# IoTSchem.net
KiCad netlist of a schematic drawn in EAGLE
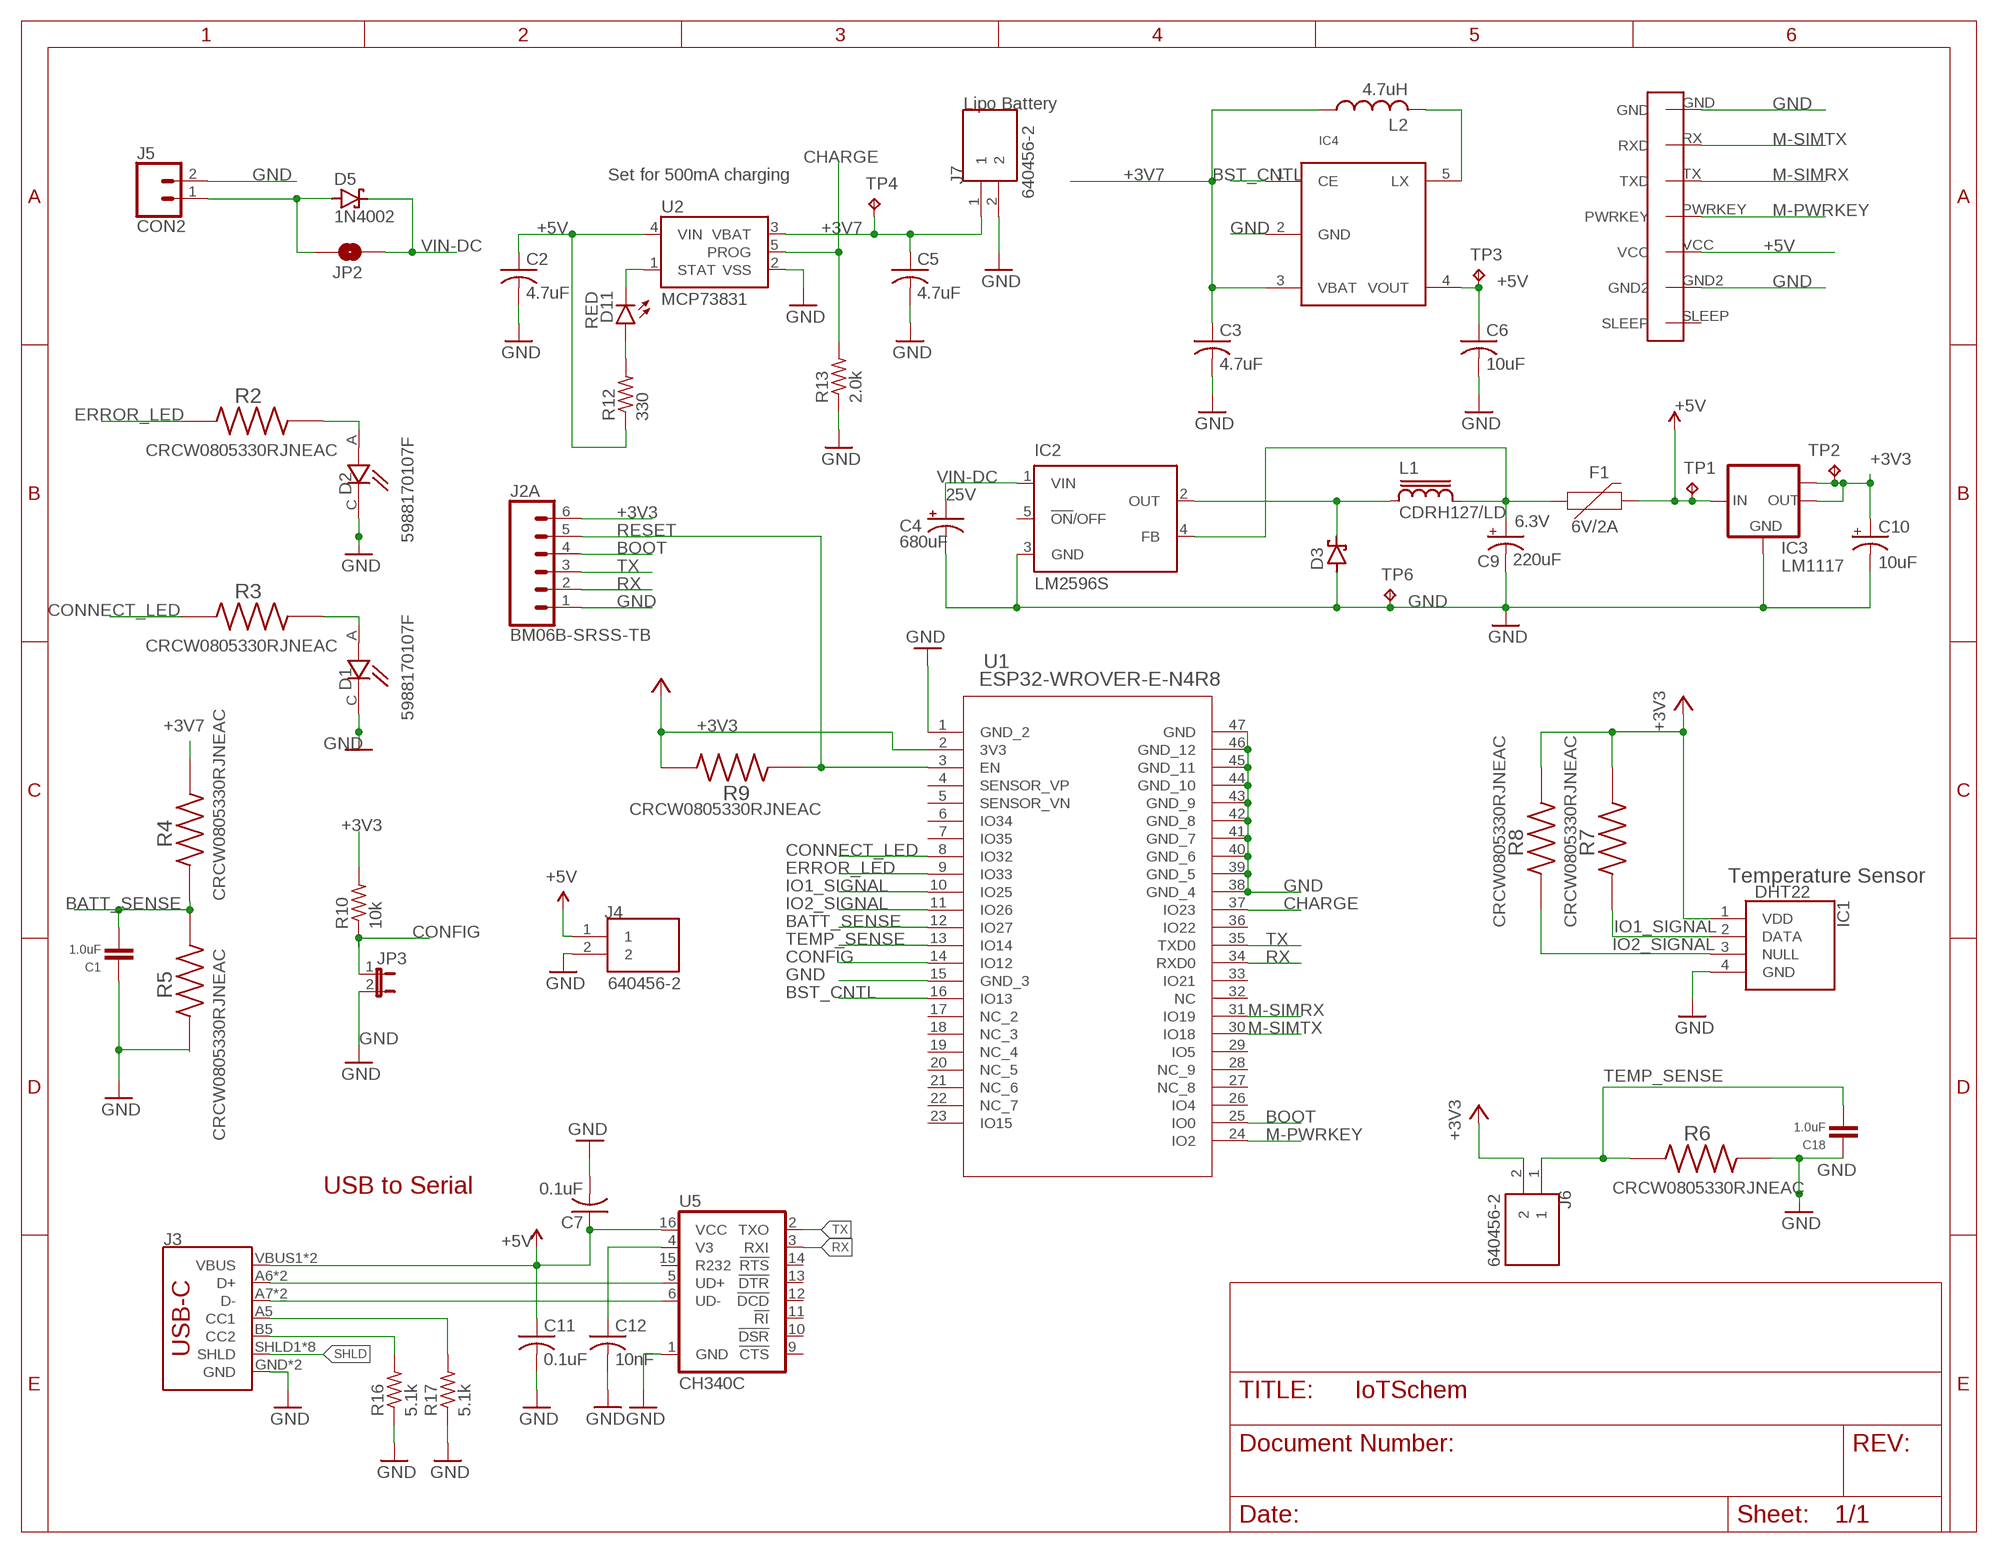
[diagram p0: schematic, sheet 1]

(export (version "E")
  (design (tool "Eeschema 10.0.6"))
  (components
    (comp (ref "C1")
      (value "1.0uF")
      (footprint "eagle-import:0805")
      (libsource (lib "eagle-import") (part "1.0UF-0805-25V-(+80/-20%)"))
    )
    (comp (ref "C2")
      (value "4.7uF")
      (footprint "eagle-import:C0603")
      (libsource (lib "eagle-import") (part "C-USC0603"))
    )
    (comp (ref "C3")
      (value "4.7uF")
      (footprint "eagle-import:C0805")
      (libsource (lib "eagle-import") (part "C-USC0805"))
    )
    (comp (ref "C4")
      (value "680uF")
      (footprint "eagle-import:E5-10,5")
      (fields (field (name "VOLTAGE") "25V"))
      (libsource (lib "eagle-import") (part "CPOL-USE5-10.5"))
    )
    (comp (ref "C5")
      (value "4.7uF")
      (footprint "eagle-import:C0603")
      (libsource (lib "eagle-import") (part "C-USC0603"))
    )
    (comp (ref "C6")
      (value "10uF")
      (footprint "eagle-import:C0805")
      (libsource (lib "eagle-import") (part "C-USC0805"))
    )
    (comp (ref "C7")
      (value "0.1uF")
      (footprint "eagle-import:C0805")
      (libsource (lib "eagle-import") (part "C-USC0805"))
    )
    (comp (ref "C9")
      (value "220uF")
      (footprint "eagle-import:UD-6,3X5,8_NICHICON")
      (fields (field (name "VOLTAGE") "6.3V"))
      (libsource (lib "eagle-import") (part "CPOL-USUD-6,3X5,8"))
    )
    (comp (ref "C10")
      (value "10uF")
      (footprint "eagle-import:EIA3216")
      (libsource (lib "eagle-import") (part "10UF-POLAR-EIA3216-16V-10%(TANT)"))
    )
    (comp (ref "C11")
      (value "0.1uF")
      (footprint "eagle-import:C0805")
      (libsource (lib "eagle-import") (part "C-USC0805"))
    )
    (comp (ref "C12")
      (value "10nF")
      (footprint "eagle-import:C0805")
      (libsource (lib "eagle-import") (part "C-USC0805"))
    )
    (comp (ref "C18")
      (value "1.0uF")
      (footprint "eagle-import:0805")
      (libsource (lib "eagle-import") (part "1.0UF-0805-25V-(+80/-20%)"))
    )
    (comp (ref "D1")
      (value "5988170107F")
      (footprint "eagle-import:LEDC2012X70N")
      (fields (field (name "DIGI-KEY_PART_NUMBER") "350-2044-1-ND") (field (name "MF") "Dialight"))
      (libsource (lib "eagle-import") (part "5988170107F"))
    )
    (comp (ref "D2")
      (value "5988170107F")
      (footprint "eagle-import:LEDC2012X70N")
      (fields (field (name "DIGI-KEY_PART_NUMBER") "350-2044-1-ND") (field (name "MF") "Dialight"))
      (libsource (lib "eagle-import") (part "5988170107F"))
    )
    (comp (ref "D3")
      (value "SCHOTTKY-DIODESMD")
      (footprint "eagle-import:SMB")
      (libsource (lib "eagle-import") (part "SCHOTTKY-DIODESMD"))
    )
    (comp (ref "D5")
      (value "1N4002")
      (footprint "eagle-import:SMB")
      (libsource (lib "eagle-import") (part "SCHOTTKY-DIODESMD"))
    )
    (comp (ref "D11")
      (value "RED")
      (footprint "eagle-import:LED-0603@1")
      (libsource (lib "eagle-import") (part "LED-RED0603"))
    )
    (comp (ref "F1")
      (value "6V/2A")
      (footprint "eagle-import:1210")
      (libsource (lib "eagle-import") (part "PPTC_6V2A"))
    )
    (comp (ref "IC1")
      (value "DHT22")
      (footprint "eagle-import:DHT22")
      (libsource (lib "eagle-import") (part "DHT22"))
    )
    (comp (ref "IC2")
      (value "LM2596S")
      (footprint "eagle-import:TO263-5")
      (fields (field (name "MF") "NATIONAL SEMICONDUCTOR") (field (name "MPN") "LM2596S-ADJ/NOPB"))
      (libsource (lib "eagle-import") (part "LM2596S"))
    )
    (comp (ref "IC3")
      (value "LM1117MPX-3.3")
      (footprint "eagle-import:SOT223")
      (libsource (lib "eagle-import") (part "LM1117MPX-3.3"))
    )
    (comp (ref "IC4")
      (value "XC9140")
      (footprint "eagle-import:SOT-25")
      (libsource (lib "eagle-import") (part "XC9140"))
    )
    (comp (ref "J1")
      (value "SIM7000A")
      (footprint "eagle-import:SIM7000A")
      (libsource (lib "eagle-import") (part "SIM7000A"))
    )
    (comp (ref "J2")
      (value "BM06B-SRSS-TB")
      (footprint "eagle-import:JST-6-SMD-HORI-1.0MM")
      (libsource (lib "eagle-import") (part "JST_6_PIN_HORIZONTAL"))
    )
    (comp (ref "J3")
      (value "USB_C16PIN")
      (footprint "eagle-import:USB-C-16P")
      (libsource (lib "eagle-import") (part "USB_C16PIN"))
    )
    (comp (ref "J4")
      (value "640456-2")
      (footprint "eagle-import:TE_640456-2")
      (fields (field (name "DIGI-KEY_PART_NUMBER") "A1921-ND") (field (name "MF") "TE Connectivity"))
      (libsource (lib "eagle-import") (part "640456-2"))
    )
    (comp (ref "J5")
      (value "CON2")
      (footprint "eagle-import:1X02")
      (libsource (lib "eagle-import") (part "CONN_02"))
    )
    (comp (ref "J6")
      (value "640456-2")
      (footprint "eagle-import:TE_640456-2")
      (fields (field (name "DIGI-KEY_PART_NUMBER") "A1921-ND") (field (name "MF") "TE Connectivity"))
      (libsource (lib "eagle-import") (part "640456-2"))
    )
    (comp (ref "J7")
      (value "640456-2")
      (footprint "eagle-import:TE_640456-2")
      (fields (field (name "DIGI-KEY_PART_NUMBER") "A1921-ND") (field (name "MF") "TE Connectivity"))
      (libsource (lib "eagle-import") (part "640456-2"))
    )
    (comp (ref "JP2")
      (value "JUMPER-SMT_2_NO_SILK")
      (footprint "eagle-import:SMT-JUMPER_2_NO_SILK")
      (libsource (lib "eagle-import") (part "JUMPER-SMT_2_NO_SILK"))
    )
    (comp (ref "JP3")
      (value "JP1E")
      (footprint "eagle-import:JP1")
      (libsource (lib "eagle-import") (part "JP1E"))
    )
    (comp (ref "L1")
      (value "CDRH127/LD")
      (footprint "eagle-import:CDRH127_LD")
      (libsource (lib "eagle-import") (part "CDRH127/LD"))
    )
    (comp (ref "L2")
      (value "4.7uH")
      (footprint "eagle-import:L2825P")
      (libsource (lib "eagle-import") (part "L-USL2825P"))
    )
    (comp (ref "R2")
      (value "CRCW0805330RJNEAC")
      (footprint "eagle-import:RESC2012X60N")
      (fields (field (name "DIGI-KEY_PART_NUMBER") "541-4168-1-ND") (field (name "MF") "Vishay"))
      (libsource (lib "eagle-import") (part "CRCW0805330RJNEAC"))
    )
    (comp (ref "R3")
      (value "CRCW0805330RJNEAC")
      (footprint "eagle-import:RESC2012X60N")
      (fields (field (name "DIGI-KEY_PART_NUMBER") "541-4168-1-ND") (field (name "MF") "Vishay"))
      (libsource (lib "eagle-import") (part "CRCW0805330RJNEAC"))
    )
    (comp (ref "R4")
      (value "CRCW0805330RJNEAC")
      (footprint "eagle-import:RESC2012X60N")
      (fields (field (name "DIGI-KEY_PART_NUMBER") "541-4168-1-ND") (field (name "MF") "Vishay"))
      (libsource (lib "eagle-import") (part "CRCW0805330RJNEAC"))
    )
    (comp (ref "R5")
      (value "CRCW0805330RJNEAC")
      (footprint "eagle-import:RESC2012X60N")
      (fields (field (name "DIGI-KEY_PART_NUMBER") "541-4168-1-ND") (field (name "MF") "Vishay"))
      (libsource (lib "eagle-import") (part "CRCW0805330RJNEAC"))
    )
    (comp (ref "R6")
      (value "CRCW0805330RJNEAC")
      (footprint "eagle-import:RESC2012X60N")
      (fields (field (name "DIGI-KEY_PART_NUMBER") "541-4168-1-ND") (field (name "MF") "Vishay"))
      (libsource (lib "eagle-import") (part "CRCW0805330RJNEAC"))
    )
    (comp (ref "R7")
      (value "CRCW0805330RJNEAC")
      (footprint "eagle-import:RESC2012X60N")
      (fields (field (name "DIGI-KEY_PART_NUMBER") "541-4168-1-ND") (field (name "MF") "Vishay"))
      (libsource (lib "eagle-import") (part "CRCW0805330RJNEAC"))
    )
    (comp (ref "R8")
      (value "CRCW0805330RJNEAC")
      (footprint "eagle-import:RESC2012X60N")
      (fields (field (name "DIGI-KEY_PART_NUMBER") "541-4168-1-ND") (field (name "MF") "Vishay"))
      (libsource (lib "eagle-import") (part "CRCW0805330RJNEAC"))
    )
    (comp (ref "R9")
      (value "CRCW0805330RJNEAC")
      (footprint "eagle-import:RESC2012X60N")
      (fields (field (name "DIGI-KEY_PART_NUMBER") "541-4168-1-ND") (field (name "MF") "Vishay"))
      (libsource (lib "eagle-import") (part "CRCW0805330RJNEAC"))
    )
    (comp (ref "R10")
      (value "10k")
      (footprint "eagle-import:R0603")
      (libsource (lib "eagle-import") (part "R-US_R0603"))
    )
    (comp (ref "R12")
      (value "330")
      (footprint "eagle-import:R0603")
      (libsource (lib "eagle-import") (part "R-US_R0603"))
    )
    (comp (ref "R13")
      (value "2.0k")
      (footprint "eagle-import:R0603")
      (libsource (lib "eagle-import") (part "R-US_R0603"))
    )
    (comp (ref "R16")
      (value "5.1k")
      (footprint "eagle-import:R0805")
      (libsource (lib "eagle-import") (part "R-US_R0805"))
    )
    (comp (ref "R17")
      (value "5.1k")
      (footprint "eagle-import:R0805")
      (libsource (lib "eagle-import") (part "R-US_R0805"))
    )
    (comp (ref "TP1")
      (value "TPB1,27")
      (footprint "eagle-import:B1,27")
      (libsource (lib "eagle-import") (part "TPB1,27"))
    )
    (comp (ref "TP2")
      (value "TPB1,27")
      (footprint "eagle-import:B1,27")
      (libsource (lib "eagle-import") (part "TPB1,27"))
    )
    (comp (ref "TP3")
      (value "TPB1,27")
      (footprint "eagle-import:B1,27")
      (libsource (lib "eagle-import") (part "TPB1,27"))
    )
    (comp (ref "TP4")
      (value "TPB1,27")
      (footprint "eagle-import:B1,27")
      (libsource (lib "eagle-import") (part "TPB1,27"))
    )
    (comp (ref "TP6")
      (value "TPB1,27")
      (footprint "eagle-import:B1,27")
      (libsource (lib "eagle-import") (part "TPB1,27"))
    )
    (comp (ref "U1")
      (value "ESP32-WROVER-E-N4R8")
      (footprint "eagle-import:ESP32­WROVER­E_ESP32­WROVER­IE")
      (fields (field (name "COPYRIGHT") "Copyright (C) 2022 Ultra Librarian. All rights reserved."))
      (libsource (lib "eagle-import") (part "ESP32-WROVER-E-N4R8"))
    )
    (comp (ref "U2")
      (value "MCP73831")
      (footprint "eagle-import:SOT23-5")
      (libsource (lib "eagle-import") (part "MCP73831"))
    )
    (comp (ref "U5")
      (value "CH340C")
      (footprint "eagle-import:SO016")
      (libsource (lib "eagle-import") (part "CH340C"))
    )
  )
  (nets
    (net (code "1") (name "+3V3") (class "Default")
      (node (ref "C10") (pin "+") (pinfunction "+_+") (pintype "passive"))
      (node (ref "IC1") (pin "1") (pinfunction "VDD_1") (pintype "bidirectional"))
      (node (ref "IC3") (pin "2") (pinfunction "OUT_2") (pintype "passive"))
      (node (ref "IC3") (pin "TAB") (pinfunction "OUT1_TAB") (pintype "passive"))
      (node (ref "J2") (pin "6") (pinfunction "6_6") (pintype "passive"))
      (node (ref "J6") (pin "2") (pinfunction "2_2") (pintype "passive"))
      (node (ref "R10") (pin "2") (pinfunction "2_2") (pintype "passive"))
      (node (ref "R7") (pin "2") (pinfunction "2_2") (pintype "passive"))
      (node (ref "R8") (pin "2") (pinfunction "2_2") (pintype "passive"))
      (node (ref "R9") (pin "2") (pinfunction "2_2") (pintype "passive"))
      (node (ref "TP2") (pin "TP") (pinfunction "TP_TP") (pintype "input"))
      (node (ref "U1") (pin "2") (pinfunction "3V3_2") (pintype "power_in"))
    )
    (net (code "2") (name "/+3V7") (class "Default")
      (node (ref "C3") (pin "1") (pinfunction "1_1") (pintype "passive"))
      (node (ref "C5") (pin "1") (pinfunction "1_1") (pintype "passive"))
      (node (ref "IC4") (pin "3") (pinfunction "VBAT_3") (pintype "bidirectional"))
      (node (ref "J7") (pin "1") (pinfunction "1_1") (pintype "passive"))
      (node (ref "L2") (pin "1") (pinfunction "1_1") (pintype "passive"))
      (node (ref "R4") (pin "2") (pinfunction "2_2") (pintype "passive"))
      (node (ref "TP4") (pin "TP") (pinfunction "TP_TP") (pintype "input"))
      (node (ref "U2") (pin "3") (pinfunction "VBAT_3") (pintype "power_in"))
    )
    (net (code "3") (name "/BATT_SENSE") (class "Default")
      (node (ref "C1") (pin "2") (pinfunction "2_2") (pintype "passive"))
      (node (ref "R4") (pin "1") (pinfunction "1_1") (pintype "passive"))
      (node (ref "R5") (pin "2") (pinfunction "2_2") (pintype "passive"))
      (node (ref "U1") (pin "12") (pinfunction "IO27_12") (pintype "bidirectional"))
    )
    (net (code "4") (name "/BOOT") (class "Default")
      (node (ref "J2") (pin "4") (pinfunction "4_4") (pintype "passive"))
      (node (ref "U1") (pin "25") (pinfunction "IO0_25") (pintype "bidirectional"))
    )
    (net (code "5") (name "/BST_CNTL") (class "Default")
      (node (ref "IC4") (pin "1") (pinfunction "CE_1") (pintype "bidirectional"))
      (node (ref "U1") (pin "16") (pinfunction "IO13_16") (pintype "bidirectional"))
    )
    (net (code "6") (name "/CHARGE") (class "Default")
      (node (ref "R13") (pin "2") (pinfunction "2_2") (pintype "passive"))
      (node (ref "U1") (pin "37") (pinfunction "IO23_37") (pintype "bidirectional"))
      (node (ref "U2") (pin "5") (pinfunction "PROG_5") (pintype "input"))
    )
    (net (code "7") (name "/CONFIG") (class "Default")
      (node (ref "JP3") (pin "1") (pinfunction "1_1") (pintype "passive"))
      (node (ref "R10") (pin "1") (pinfunction "1_1") (pintype "passive"))
      (node (ref "U1") (pin "14") (pinfunction "IO12_14") (pintype "bidirectional"))
    )
    (net (code "8") (name "/CONNECT_LED") (class "Default")
      (node (ref "R3") (pin "1") (pinfunction "1_1") (pintype "passive"))
      (node (ref "U1") (pin "8") (pinfunction "IO32_8") (pintype "bidirectional"))
    )
    (net (code "9") (name "/ERROR_LED") (class "Default")
      (node (ref "R2") (pin "1") (pinfunction "1_1") (pintype "passive"))
      (node (ref "U1") (pin "9") (pinfunction "IO33_9") (pintype "bidirectional"))
    )
    (net (code "10") (name "/IO1_SIGNAL") (class "Default")
      (node (ref "IC1") (pin "2") (pinfunction "DATA_2") (pintype "bidirectional"))
      (node (ref "R7") (pin "1") (pinfunction "1_1") (pintype "passive"))
      (node (ref "U1") (pin "10") (pinfunction "IO25_10") (pintype "bidirectional"))
    )
    (net (code "11") (name "/IO2_SIGNAL") (class "Default")
      (node (ref "IC1") (pin "3") (pinfunction "NULL_3") (pintype "bidirectional"))
      (node (ref "R8") (pin "1") (pinfunction "1_1") (pintype "passive"))
      (node (ref "U1") (pin "11") (pinfunction "IO26_11") (pintype "bidirectional"))
    )
    (net (code "12") (name "/M-PWRKEY") (class "Default")
      (node (ref "J1") (pin "PWRKEY") (pinfunction "PWRKEY_PWRKEY") (pintype "bidirectional"))
      (node (ref "U1") (pin "24") (pinfunction "IO2_24") (pintype "bidirectional"))
    )
    (net (code "13") (name "/M-SIMRX") (class "Default")
      (node (ref "J1") (pin "TX") (pinfunction "TXD_TX") (pintype "bidirectional"))
      (node (ref "U1") (pin "31") (pinfunction "IO19_31") (pintype "bidirectional"))
    )
    (net (code "14") (name "/M-SIMTX") (class "Default")
      (node (ref "J1") (pin "RX") (pinfunction "RXD_RX") (pintype "bidirectional"))
      (node (ref "U1") (pin "30") (pinfunction "IO18_30") (pintype "bidirectional"))
    )
    (net (code "15") (name "/RESET") (class "Default")
      (node (ref "J2") (pin "5") (pinfunction "5_5") (pintype "passive"))
      (node (ref "R9") (pin "1") (pinfunction "1_1") (pintype "passive"))
      (node (ref "U1") (pin "3") (pinfunction "EN_3") (pintype "input"))
    )
    (net (code "16") (name "/TEMP_SENSE") (class "Default")
      (node (ref "C18") (pin "2") (pinfunction "2_2") (pintype "passive"))
      (node (ref "J6") (pin "1") (pinfunction "1_1") (pintype "passive"))
      (node (ref "R6") (pin "1") (pinfunction "1_1") (pintype "passive"))
      (node (ref "U1") (pin "13") (pinfunction "IO14_13") (pintype "bidirectional"))
    )
    (net (code "17") (name "/VIN-DC") (class "Default")
      (node (ref "C4") (pin "+") (pinfunction "+_+") (pintype "passive"))
      (node (ref "D5") (pin "C") (pinfunction "C_C") (pintype "passive"))
      (node (ref "IC2") (pin "1") (pinfunction "VIN_1") (pintype "input"))
      (node (ref "JP2") (pin "2") (pinfunction "2_2") (pintype "passive"))
    )
    (net (code "18") (name "5V") (class "Default")
      (node (ref "C11") (pin "1") (pinfunction "1_1") (pintype "passive"))
      (node (ref "C2") (pin "1") (pinfunction "1_1") (pintype "passive"))
      (node (ref "C6") (pin "1") (pinfunction "1_1") (pintype "passive"))
      (node (ref "C7") (pin "1") (pinfunction "1_1") (pintype "passive"))
      (node (ref "F1") (pin "2") (pinfunction "2_2") (pintype "bidirectional"))
      (node (ref "IC3") (pin "3") (pinfunction "IN_3") (pintype "input"))
      (node (ref "IC4") (pin "4") (pinfunction "VOUT_4") (pintype "bidirectional"))
      (node (ref "J1") (pin "VCC") (pinfunction "VCC_VCC") (pintype "bidirectional"))
      (node (ref "J3") (pin "VBUS1") (pinfunction "VBUS_VBUS1") (pintype "bidirectional"))
      (node (ref "J3") (pin "VBUS2") (pinfunction "VBUS_VBUS2") (pintype "bidirectional"))
      (node (ref "J4") (pin "1") (pinfunction "1_1") (pintype "passive"))
      (node (ref "R12") (pin "1") (pinfunction "1_1") (pintype "passive"))
      (node (ref "TP1") (pin "TP") (pinfunction "TP_TP") (pintype "input"))
      (node (ref "TP3") (pin "TP") (pinfunction "TP_TP") (pintype "input"))
      (node (ref "U2") (pin "4") (pinfunction "VIN_4") (pintype "power_in"))
      (node (ref "U5") (pin "16") (pinfunction "VCC_16") (pintype "bidirectional"))
    )
    (net (code "19") (name "GND") (class "Default")
      (node (ref "C1") (pin "1") (pinfunction "1_1") (pintype "passive"))
      (node (ref "C10") (pin "-") (pinfunction "-_-") (pintype "passive"))
      (node (ref "C11") (pin "2") (pinfunction "2_2") (pintype "passive"))
      (node (ref "C12") (pin "2") (pinfunction "2_2") (pintype "passive"))
      (node (ref "C18") (pin "1") (pinfunction "1_1") (pintype "passive"))
      (node (ref "C2") (pin "2") (pinfunction "2_2") (pintype "passive"))
      (node (ref "C3") (pin "2") (pinfunction "2_2") (pintype "passive"))
      (node (ref "C4") (pin "-") (pinfunction "-_-") (pintype "passive"))
      (node (ref "C5") (pin "2") (pinfunction "2_2") (pintype "passive"))
      (node (ref "C6") (pin "2") (pinfunction "2_2") (pintype "passive"))
      (node (ref "C7") (pin "2") (pinfunction "2_2") (pintype "passive"))
      (node (ref "C9") (pin "-") (pinfunction "-_-") (pintype "passive"))
      (node (ref "D1") (pin "C") (pinfunction "C_C") (pintype "passive"))
      (node (ref "D2") (pin "C") (pinfunction "C_C") (pintype "passive"))
      (node (ref "D3") (pin "A") (pinfunction "A_A") (pintype "passive"))
      (node (ref "IC1") (pin "4") (pinfunction "GND_4") (pintype "bidirectional"))
      (node (ref "IC2") (pin "3") (pinfunction "GND_3") (pintype "power_in"))
      (node (ref "IC3") (pin "1") (pinfunction "GND_1") (pintype "input"))
      (node (ref "IC4") (pin "2") (pinfunction "GND_2") (pintype "bidirectional"))
      (node (ref "J1") (pin "GND") (pinfunction "GND_GND") (pintype "bidirectional"))
      (node (ref "J1") (pin "GND2") (pinfunction "GND2_GND2") (pintype "bidirectional"))
      (node (ref "J2") (pin "1") (pinfunction "1_1") (pintype "passive"))
      (node (ref "J3") (pin "GND") (pinfunction "GND_GND") (pintype "bidirectional"))
      (node (ref "J3") (pin "GND2") (pinfunction "GND_GND2") (pintype "bidirectional"))
      (node (ref "J4") (pin "2") (pinfunction "2_2") (pintype "passive"))
      (node (ref "J5") (pin "2") (pinfunction "2_2") (pintype "passive"))
      (node (ref "J7") (pin "2") (pinfunction "2_2") (pintype "passive"))
      (node (ref "JP3") (pin "2") (pinfunction "2_2") (pintype "passive"))
      (node (ref "R13") (pin "1") (pinfunction "1_1") (pintype "passive"))
      (node (ref "R16") (pin "1") (pinfunction "1_1") (pintype "passive"))
      (node (ref "R17") (pin "1") (pinfunction "1_1") (pintype "passive"))
      (node (ref "R5") (pin "1") (pinfunction "1_1") (pintype "passive"))
      (node (ref "R6") (pin "2") (pinfunction "2_2") (pintype "passive"))
      (node (ref "TP6") (pin "TP") (pinfunction "TP_TP") (pintype "input"))
      (node (ref "U1") (pin "1") (pinfunction "GND_2_1") (pintype "passive"))
      (node (ref "U1") (pin "15") (pinfunction "GND_3_15") (pintype "passive"))
      (node (ref "U1") (pin "38") (pinfunction "GND_4_38") (pintype "passive"))
      (node (ref "U1") (pin "39") (pinfunction "GND_5_39") (pintype "passive"))
      (node (ref "U1") (pin "40") (pinfunction "GND_6_40") (pintype "passive"))
      (node (ref "U1") (pin "41") (pinfunction "GND_7_41") (pintype "passive"))
      (node (ref "U1") (pin "42") (pinfunction "GND_8_42") (pintype "passive"))
      (node (ref "U1") (pin "43") (pinfunction "GND_9_43") (pintype "passive"))
      (node (ref "U1") (pin "44") (pinfunction "GND_10_44") (pintype "passive"))
      (node (ref "U1") (pin "45") (pinfunction "GND_11_45") (pintype "passive"))
      (node (ref "U1") (pin "46") (pinfunction "GND_12_46") (pintype "passive"))
      (node (ref "U1") (pin "47") (pinfunction "GND_47") (pintype "passive"))
      (node (ref "U2") (pin "2") (pinfunction "VSS_2") (pintype "power_in"))
      (node (ref "U5") (pin "1") (pinfunction "GND_1") (pintype "bidirectional"))
    )
    (net (code "20") (name "Net-(D1-PadA)") (class "Default")
      (node (ref "D1") (pin "A") (pinfunction "A_A") (pintype "passive"))
      (node (ref "R3") (pin "2") (pinfunction "2_2") (pintype "passive"))
    )
    (net (code "21") (name "Net-(D2-PadA)") (class "Default")
      (node (ref "D2") (pin "A") (pinfunction "A_A") (pintype "passive"))
      (node (ref "R2") (pin "2") (pinfunction "2_2") (pintype "passive"))
    )
    (net (code "22") (name "Net-(D5-PadA)") (class "Default")
      (node (ref "D5") (pin "A") (pinfunction "A_A") (pintype "passive"))
      (node (ref "J5") (pin "1") (pinfunction "1_1") (pintype "passive"))
      (node (ref "JP2") (pin "1") (pinfunction "1_1") (pintype "passive"))
    )
    (net (code "23") (name "Net-(D11-PadA)") (class "Default")
      (node (ref "D11") (pin "A") (pinfunction "A_A") (pintype "passive"))
      (node (ref "R12") (pin "2") (pinfunction "2_2") (pintype "passive"))
    )
    (net (code "24") (name "Net-(IC2-FB)") (class "Default")
      (node (ref "C9") (pin "+") (pinfunction "+_+") (pintype "passive"))
      (node (ref "F1") (pin "1") (pinfunction "1_1") (pintype "bidirectional"))
      (node (ref "IC2") (pin "4") (pinfunction "FB_4") (pintype "input"))
      (node (ref "L1") (pin "2") (pinfunction "2_2") (pintype "passive"))
    )
    (net (code "25") (name "Net-(IC2-OUT)") (class "Default")
      (node (ref "D3") (pin "C") (pinfunction "C_C") (pintype "passive"))
      (node (ref "IC2") (pin "2") (pinfunction "OUT_2") (pintype "output"))
      (node (ref "L1") (pin "1") (pinfunction "1_1") (pintype "passive"))
    )
    (net (code "26") (name "Net-(IC4-LX)") (class "Default")
      (node (ref "IC4") (pin "5") (pinfunction "LX_5") (pintype "bidirectional"))
      (node (ref "L2") (pin "2") (pinfunction "2_2") (pintype "passive"))
    )
    (net (code "27") (name "Net-(J3-CC1)") (class "Default")
      (node (ref "J3") (pin "A5") (pinfunction "CC1_A5") (pintype "bidirectional"))
      (node (ref "R17") (pin "2") (pinfunction "2_2") (pintype "passive"))
    )
    (net (code "28") (name "Net-(J3-CC2)") (class "Default")
      (node (ref "J3") (pin "B5") (pinfunction "CC2_B5") (pintype "bidirectional"))
      (node (ref "R16") (pin "2") (pinfunction "2_2") (pintype "passive"))
    )
    (net (code "29") (name "Net-(U2-STAT)") (class "Default")
      (node (ref "D11") (pin "C") (pinfunction "C_C") (pintype "passive"))
      (node (ref "U2") (pin "1") (pinfunction "STAT_1") (pintype "output"))
    )
    (net (code "30") (name "Net-(U5-UD+)") (class "Default")
      (node (ref "J3") (pin "A6") (pinfunction "D+_A6") (pintype "bidirectional"))
      (node (ref "J3") (pin "B6") (pinfunction "D+_B6") (pintype "bidirectional"))
      (node (ref "U5") (pin "5") (pinfunction "UD+_5") (pintype "bidirectional"))
    )
    (net (code "31") (name "Net-(U5-UD-)") (class "Default")
      (node (ref "J3") (pin "A7") (pinfunction "D-_A7") (pintype "bidirectional"))
      (node (ref "J3") (pin "B7") (pinfunction "D-_B7") (pintype "bidirectional"))
      (node (ref "U5") (pin "6") (pinfunction "UD-_6") (pintype "bidirectional"))
    )
    (net (code "32") (name "Net-(U5-V3)") (class "Default")
      (node (ref "C12") (pin "1") (pinfunction "1_1") (pintype "passive"))
      (node (ref "U5") (pin "4") (pinfunction "V3_4") (pintype "bidirectional"))
    )
    (net (code "33") (name "RX") (class "Default")
      (node (ref "J2") (pin "2") (pinfunction "2_2") (pintype "passive"))
      (node (ref "U1") (pin "34") (pinfunction "RXD0_34") (pintype "bidirectional"))
      (node (ref "U5") (pin "3") (pinfunction "RXI_3") (pintype "bidirectional"))
    )
    (net (code "34") (name "SHLD") (class "Default")
      (node (ref "J3") (pin "SHLD1") (pinfunction "SHLD_SHLD1") (pintype "bidirectional"))
      (node (ref "J3") (pin "SHLD2") (pinfunction "SHLD_SHLD2") (pintype "bidirectional"))
      (node (ref "J3") (pin "SHLD3") (pinfunction "SHLD_SHLD3") (pintype "bidirectional"))
      (node (ref "J3") (pin "SHLD4") (pinfunction "SHLD_SHLD4") (pintype "bidirectional"))
      (node (ref "J3") (pin "SHLD5") (pinfunction "SHLD_SHLD5") (pintype "bidirectional"))
      (node (ref "J3") (pin "SHLD6") (pinfunction "SHLD_SHLD6") (pintype "bidirectional"))
      (node (ref "J3") (pin "SHLD7") (pinfunction "SHLD_SHLD7") (pintype "bidirectional"))
      (node (ref "J3") (pin "SHLD8") (pinfunction "SHLD_SHLD8") (pintype "bidirectional"))
    )
    (net (code "35") (name "TX") (class "Default")
      (node (ref "J2") (pin "3") (pinfunction "3_3") (pintype "passive"))
      (node (ref "U1") (pin "35") (pinfunction "TXD0_35") (pintype "bidirectional"))
      (node (ref "U5") (pin "2") (pinfunction "TXO_2") (pintype "bidirectional"))
    )
    (net (code "36") (name "unconnected-(IC2-~{ON}{slash}OFF-Pad5)") (class "Default")
      (node (ref "IC2") (pin "5") (pinfunction "~{ON}/OFF_5") (pintype "input"))
    )
    (net (code "37") (name "unconnected-(J1-PadSLEEP)") (class "Default")
      (node (ref "J1") (pin "SLEEP") (pinfunction "SLEEP_SLEEP") (pintype "bidirectional"))
    )
    (net (code "38") (name "unconnected-(U1-IO4-Pad26)") (class "Default")
      (node (ref "U1") (pin "26") (pinfunction "IO4_26") (pintype "bidirectional"))
    )
    (net (code "39") (name "unconnected-(U1-IO5-Pad29)") (class "Default")
      (node (ref "U1") (pin "29") (pinfunction "IO5_29") (pintype "bidirectional"))
    )
    (net (code "40") (name "unconnected-(U1-IO15-Pad23)") (class "Default")
      (node (ref "U1") (pin "23") (pinfunction "IO15_23") (pintype "bidirectional"))
    )
    (net (code "41") (name "unconnected-(U1-IO21-Pad33)") (class "Default")
      (node (ref "U1") (pin "33") (pinfunction "IO21_33") (pintype "bidirectional"))
    )
    (net (code "42") (name "unconnected-(U1-IO22-Pad36)") (class "Default")
      (node (ref "U1") (pin "36") (pinfunction "IO22_36") (pintype "bidirectional"))
    )
    (net (code "43") (name "unconnected-(U1-IO34-Pad6)") (class "Default")
      (node (ref "U1") (pin "6") (pinfunction "IO34_6") (pintype "input"))
    )
    (net (code "44") (name "unconnected-(U1-IO35-Pad7)") (class "Default")
      (node (ref "U1") (pin "7") (pinfunction "IO35_7") (pintype "input"))
    )
    (net (code "45") (name "unconnected-(U1-NC-Pad32)") (class "Default")
      (node (ref "U1") (pin "32") (pinfunction "NC_32") (pintype "no_connect"))
    )
    (net (code "46") (name "unconnected-(U1-NC_2-Pad17)") (class "Default")
      (node (ref "U1") (pin "17") (pinfunction "NC_2_17") (pintype "no_connect"))
    )
    (net (code "47") (name "unconnected-(U1-NC_3-Pad18)") (class "Default")
      (node (ref "U1") (pin "18") (pinfunction "NC_3_18") (pintype "no_connect"))
    )
    (net (code "48") (name "unconnected-(U1-NC_4-Pad19)") (class "Default")
      (node (ref "U1") (pin "19") (pinfunction "NC_4_19") (pintype "no_connect"))
    )
    (net (code "49") (name "unconnected-(U1-NC_5-Pad20)") (class "Default")
      (node (ref "U1") (pin "20") (pinfunction "NC_5_20") (pintype "no_connect"))
    )
    (net (code "50") (name "unconnected-(U1-NC_6-Pad21)") (class "Default")
      (node (ref "U1") (pin "21") (pinfunction "NC_6_21") (pintype "no_connect"))
    )
    (net (code "51") (name "unconnected-(U1-NC_7-Pad22)") (class "Default")
      (node (ref "U1") (pin "22") (pinfunction "NC_7_22") (pintype "no_connect"))
    )
    (net (code "52") (name "unconnected-(U1-NC_8-Pad27)") (class "Default")
      (node (ref "U1") (pin "27") (pinfunction "NC_8_27") (pintype "no_connect"))
    )
    (net (code "53") (name "unconnected-(U1-NC_9-Pad28)") (class "Default")
      (node (ref "U1") (pin "28") (pinfunction "NC_9_28") (pintype "no_connect"))
    )
    (net (code "54") (name "unconnected-(U1-SENSOR_VN-Pad5)") (class "Default")
      (node (ref "U1") (pin "5") (pinfunction "SENSOR_VN_5") (pintype "input"))
    )
    (net (code "55") (name "unconnected-(U1-SENSOR_VP-Pad4)") (class "Default")
      (node (ref "U1") (pin "4") (pinfunction "SENSOR_VP_4") (pintype "input"))
    )
    (net (code "56") (name "unconnected-(U5-R232-Pad15)") (class "Default")
      (node (ref "U5") (pin "15") (pinfunction "R232_15") (pintype "bidirectional"))
    )
    (net (code "57") (name "unconnected-(U5-~{CTS}-Pad9)") (class "Default")
      (node (ref "U5") (pin "9") (pinfunction "~{CTS}_9") (pintype "bidirectional"))
    )
    (net (code "58") (name "unconnected-(U5-~{DCD}-Pad12)") (class "Default")
      (node (ref "U5") (pin "12") (pinfunction "~{DCD}_12") (pintype "bidirectional"))
    )
    (net (code "59") (name "unconnected-(U5-~{DSR}-Pad10)") (class "Default")
      (node (ref "U5") (pin "10") (pinfunction "~{DSR}_10") (pintype "bidirectional"))
    )
    (net (code "60") (name "unconnected-(U5-~{DTR}-Pad13)") (class "Default")
      (node (ref "U5") (pin "13") (pinfunction "~{DTR}_13") (pintype "bidirectional"))
    )
    (net (code "61") (name "unconnected-(U5-~{RI}-Pad11)") (class "Default")
      (node (ref "U5") (pin "11") (pinfunction "~{RI}_11") (pintype "bidirectional"))
    )
    (net (code "62") (name "unconnected-(U5-~{RTS}-Pad14)") (class "Default")
      (node (ref "U5") (pin "14") (pinfunction "~{RTS}_14") (pintype "bidirectional"))
    )
  )
)
